# Boost.net
KiCad netlist of a schematic drawn in Altium Designer
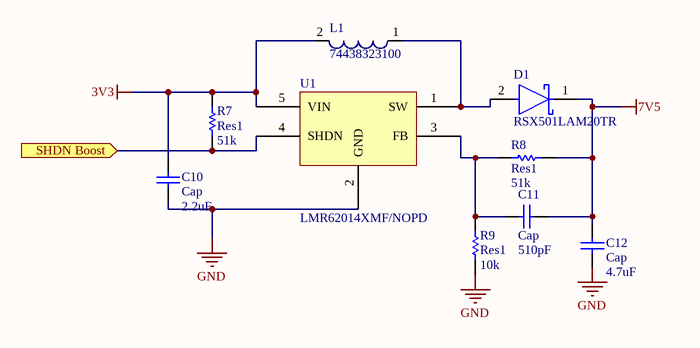
[diagram p0: Boost.SchDoc]

(export (version "E")
  (design (tool "Eeschema 10.0.6"))
  (components
    (comp (ref "C10")
      (value "Cap")
      (footprint "1608[0603]")
      (description "Capacitor")
      (fields (field (name "ALTIUM_VALUE") "2.2uF") (field (name "PUBLISHER") "Altium Limited"))
      (libsource (lib "Miscellaneous Devices") (part "Cap"))
    )
    (comp (ref "C11")
      (value "Cap")
      (footprint "6-0805_M")
      (description "Capacitor")
      (fields (field (name "ALTIUM_VALUE") "510pF") (field (name "PUBLISHER") "Altium Limited"))
      (libsource (lib "Miscellaneous Devices") (part "Cap"))
    )
    (comp (ref "C12")
      (value "Cap")
      (footprint "6-0805_M")
      (description "Capacitor")
      (fields (field (name "ALTIUM_VALUE") "4.7uF") (field (name "PUBLISHER") "Altium Limited"))
      (libsource (lib "Miscellaneous Devices") (part "Cap"))
    )
    (comp (ref "D1")
      (value "RSX501LAM20TR")
      (footprint "FP-PMDTM-MFG")
      (description "Diode Schottky 20V 5A Surface Mount PMDTM")
      (fields (field (name "OCTOPART") "https://octopart.com/rsx501lam20tr-rohm-82270774"))
      (libsource (lib "Altium Content Vault") (part "1d6ec82d83fb6aee721767c19dac4b9"))
    )
    (comp (ref "L1")
      (value "74438323100")
      (footprint "SMD 2510")
      (description "Power Multilayer Inductor WE-MAPI, L=10.0µH")
      (fields (field (name "MANUFACTURER") "Wuerth Elektronik"))
      (libsource (lib "Altium Content Vault") (part "WE-IND-INDUCTOR-2"))
    )
    (comp (ref "R7")
      (value "Res1")
      (footprint "1608[0603]")
      (description "Resistor")
      (fields (field (name "ALTIUM_VALUE") "51k") (field (name "PUBLISHER") "Altium Limited"))
      (libsource (lib "Miscellaneous Devices") (part "Res1"))
    )
    (comp (ref "R8")
      (value "Res1")
      (footprint "1608[0603]")
      (description "Resistor")
      (fields (field (name "ALTIUM_VALUE") "51k") (field (name "PUBLISHER") "Altium Limited"))
      (libsource (lib "Miscellaneous Devices") (part "Res1"))
    )
    (comp (ref "R9")
      (value "Res1")
      (footprint "0402-A")
      (description "Resistor")
      (fields (field (name "ALTIUM_VALUE") "10k") (field (name "PUBLISHER") "Altium Limited"))
      (libsource (lib "Miscellaneous Devices") (part "Res1"))
    )
    (comp (ref "U1")
      (value "LMR62014XMF/NOPD")
      (footprint "SOT95P280X145-5N")
      (libsource (lib "BPDC Library") (part "LMR62014XMF/NOPD"))
    )
  )
  (nets
    (net (code "1") (name "/SHDN Boost") (class "Default")
      (node (ref "R7") (pin "2") (pinfunction "2_2") (pintype "passive"))
      (node (ref "U1") (pin "4") (pinfunction "SHDN_4") (pintype "passive"))
    )
    (net (code "2") (name "3V3") (class "Default")
      (node (ref "C10") (pin "2") (pinfunction "2_2") (pintype "passive"))
      (node (ref "L1") (pin "2") (pinfunction "2_2") (pintype "passive"))
      (node (ref "R7") (pin "1") (pinfunction "1_1") (pintype "passive"))
      (node (ref "U1") (pin "5") (pinfunction "VIN_5") (pintype "passive"))
    )
    (net (code "3") (name "7V5") (class "Default")
      (node (ref "C11") (pin "1") (pinfunction "1_1") (pintype "passive"))
      (node (ref "C12") (pin "2") (pinfunction "2_2") (pintype "passive"))
      (node (ref "D1") (pin "1") (pinfunction "C_1") (pintype "passive"))
      (node (ref "R8") (pin "2") (pinfunction "2_2") (pintype "passive"))
    )
    (net (code "4") (name "GND") (class "Default")
      (node (ref "C10") (pin "1") (pinfunction "1_1") (pintype "passive"))
      (node (ref "C12") (pin "1") (pinfunction "1_1") (pintype "passive"))
      (node (ref "R9") (pin "2") (pinfunction "2_2") (pintype "passive"))
      (node (ref "U1") (pin "2") (pinfunction "GND_2") (pintype "passive"))
    )
    (net (code "5") (name "Net-(D1-A)") (class "Default")
      (node (ref "D1") (pin "2") (pinfunction "A_2") (pintype "passive"))
      (node (ref "L1") (pin "1") (pinfunction "1_1") (pintype "passive"))
      (node (ref "U1") (pin "1") (pinfunction "SW_1") (pintype "passive"))
    )
    (net (code "6") (name "Net-(U1-FB)") (class "Default")
      (node (ref "C11") (pin "2") (pinfunction "2_2") (pintype "passive"))
      (node (ref "R8") (pin "1") (pinfunction "1_1") (pintype "passive"))
      (node (ref "R9") (pin "1") (pinfunction "1_1") (pintype "passive"))
      (node (ref "U1") (pin "3") (pinfunction "FB_3") (pintype "passive"))
    )
  )
)
